# Optoisolator_Relay.net
KiCad netlist of a schematic drawn in EAGLE
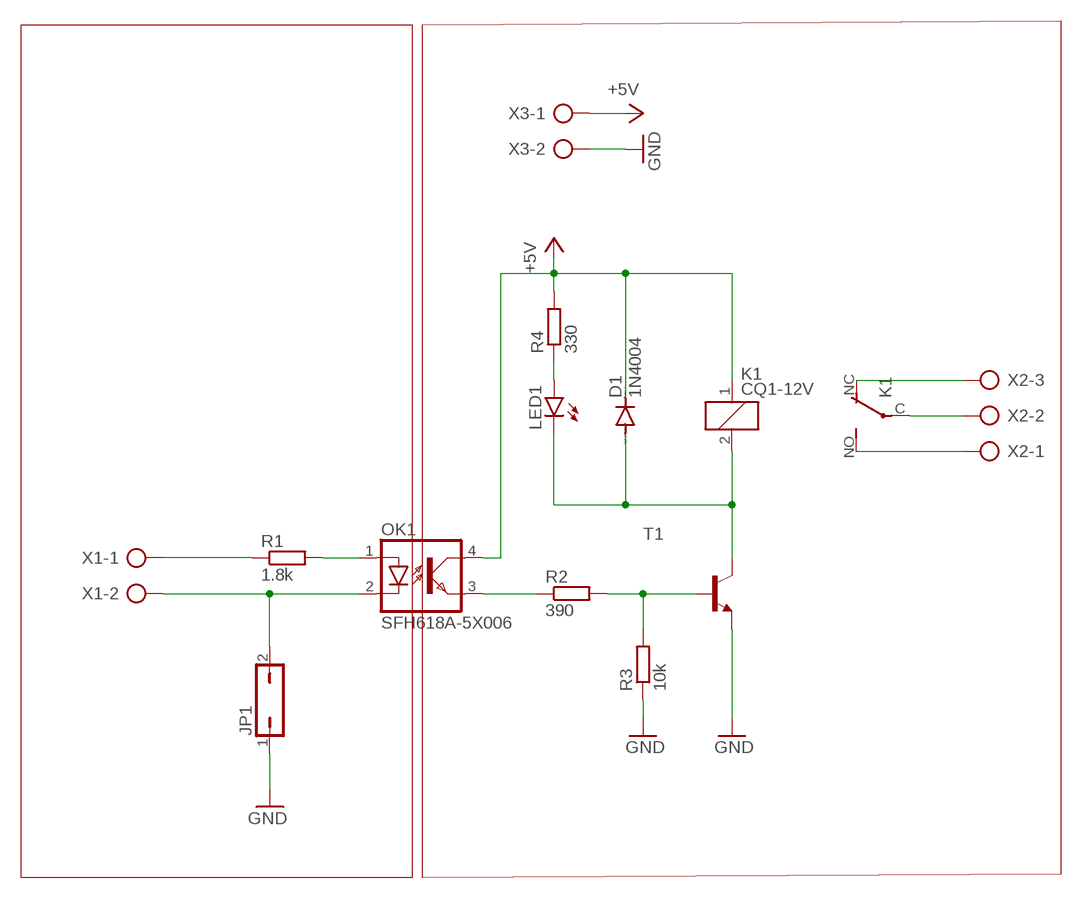
[diagram p0: schematic, sheet 1]

(export (version "E")
  (design (tool "Eeschema 10.0.6"))
  (components
    (comp (ref "D1")
      (value "1N4004")
      (footprint "eagle-import:DO41-10")
      (libsource (lib "eagle-import") (part "1N4004"))
    )
    (comp (ref "JP1")
      (value "JP1Q")
      (footprint "eagle-import:JP1")
      (libsource (lib "eagle-import") (part "JP1Q"))
    )
    (comp (ref "K1")
      (value "CQ1-12V")
      (footprint "eagle-import:CQ1")
      (libsource (lib "eagle-import") (part "CQ1-12V"))
    )
    (comp (ref "LED1")
      (value "LED3MM")
      (footprint "eagle-import:LED3MM")
      (libsource (lib "eagle-import") (part "LED3MM"))
    )
    (comp (ref "OK1")
      (value "SFH618A-5X006")
      (footprint "eagle-import:DIP4-400")
      (libsource (lib "eagle-import") (part "SFH618?A-5X006"))
    )
    (comp (ref "R1")
      (value "1.8k")
      (footprint "eagle-import:0204_7")
      (libsource (lib "eagle-import") (part "R-EU_0204/7"))
    )
    (comp (ref "R2")
      (value "390")
      (footprint "eagle-import:0204_7")
      (libsource (lib "eagle-import") (part "R-EU_0204/7"))
    )
    (comp (ref "R3")
      (value "10k")
      (footprint "eagle-import:0204_7")
      (libsource (lib "eagle-import") (part "R-EU_0204/7"))
    )
    (comp (ref "R4")
      (value "330")
      (footprint "eagle-import:0204_7")
      (libsource (lib "eagle-import") (part "R-EU_0204/7"))
    )
    (comp (ref "T1")
      (value "2N2222-NPN-TO92-EBC")
      (footprint "eagle-import:TO92-EBC")
      (libsource (lib "eagle-import") (part "-NPN-TO92-EBC2N2222"))
    )
    (comp (ref "X1")
      (value "AK300/2")
      (footprint "eagle-import:AK300_2")
      (libsource (lib "eagle-import") (part "AK300/2"))
    )
    (comp (ref "X2")
      (value "AK300/3")
      (footprint "eagle-import:AK300_3")
      (libsource (lib "eagle-import") (part "AK300/3"))
    )
    (comp (ref "X3")
      (value "AK300/2")
      (footprint "eagle-import:AK300_2")
      (libsource (lib "eagle-import") (part "AK300/2"))
    )
  )
  (nets
    (net (code "1") (name "+5V") (class "Default")
      (node (ref "D1") (pin "C") (pinfunction "C_C") (pintype "passive"))
      (node (ref "K1") (pin "1") (pinfunction "1_1") (pintype "passive"))
      (node (ref "OK1") (pin "4") (pinfunction "COL_4") (pintype "passive"))
      (node (ref "R4") (pin "2") (pinfunction "2_2") (pintype "passive"))
      (node (ref "X3") (pin "1") (pinfunction "KL_1") (pintype "passive"))
    )
    (net (code "2") (name "GND") (class "Default")
      (node (ref "JP1") (pin "1") (pinfunction "1_1") (pintype "passive"))
      (node (ref "R3") (pin "1") (pinfunction "1_1") (pintype "passive"))
      (node (ref "T1") (pin "E") (pinfunction "E_E") (pintype "passive"))
      (node (ref "X3") (pin "2") (pinfunction "KL_2") (pintype "passive"))
    )
    (net (code "3") (name "Net-(K1B-O)") (class "Default")
      (node (ref "K1") (pin "NC") (pinfunction "O_NC") (pintype "passive"))
      (node (ref "X2") (pin "3") (pinfunction "KL_3") (pintype "passive"))
    )
    (net (code "4") (name "Net-(K1B-P)") (class "Default")
      (node (ref "K1") (pin "C") (pinfunction "P_C") (pintype "passive"))
      (node (ref "X2") (pin "2") (pinfunction "KL_2") (pintype "passive"))
    )
    (net (code "5") (name "Net-(K1B-S)") (class "Default")
      (node (ref "K1") (pin "NO") (pinfunction "S_NO") (pintype "passive"))
      (node (ref "X2") (pin "1") (pinfunction "KL_1") (pintype "passive"))
    )
    (net (code "6") (name "Net-(LED1-C)") (class "Default")
      (node (ref "D1") (pin "A") (pinfunction "A_A") (pintype "passive"))
      (node (ref "K1") (pin "2") (pinfunction "2_2") (pintype "passive"))
      (node (ref "LED1") (pin "K") (pinfunction "C_K") (pintype "passive"))
      (node (ref "T1") (pin "C") (pinfunction "C_C") (pintype "passive"))
    )
    (net (code "7") (name "Net-(LED1-PadA)") (class "Default")
      (node (ref "LED1") (pin "A") (pinfunction "A_A") (pintype "passive"))
      (node (ref "R4") (pin "1") (pinfunction "1_1") (pintype "passive"))
    )
    (net (code "8") (name "Net-(OK1-A)") (class "Default")
      (node (ref "OK1") (pin "1") (pinfunction "A_1") (pintype "passive"))
      (node (ref "R1") (pin "2") (pinfunction "2_2") (pintype "passive"))
    )
    (net (code "9") (name "Net-(OK1-C)") (class "Default")
      (node (ref "JP1") (pin "2") (pinfunction "2_2") (pintype "passive"))
      (node (ref "OK1") (pin "2") (pinfunction "C_2") (pintype "passive"))
      (node (ref "X1") (pin "2") (pinfunction "KL_2") (pintype "passive"))
    )
    (net (code "10") (name "Net-(OK1-EMIT)") (class "Default")
      (node (ref "OK1") (pin "3") (pinfunction "EMIT_3") (pintype "passive"))
      (node (ref "R2") (pin "1") (pinfunction "1_1") (pintype "passive"))
    )
    (net (code "11") (name "Net-(R2-Pad2)") (class "Default")
      (node (ref "R2") (pin "2") (pinfunction "2_2") (pintype "passive"))
      (node (ref "R3") (pin "2") (pinfunction "2_2") (pintype "passive"))
      (node (ref "T1") (pin "B") (pinfunction "B_B") (pintype "passive"))
    )
    (net (code "12") (name "Net-(X1A-KL)") (class "Default")
      (node (ref "R1") (pin "1") (pinfunction "1_1") (pintype "passive"))
      (node (ref "X1") (pin "1") (pinfunction "KL_1") (pintype "passive"))
    )
  )
)
